# shield_v9.net
KiCad netlist of a schematic drawn in EAGLE
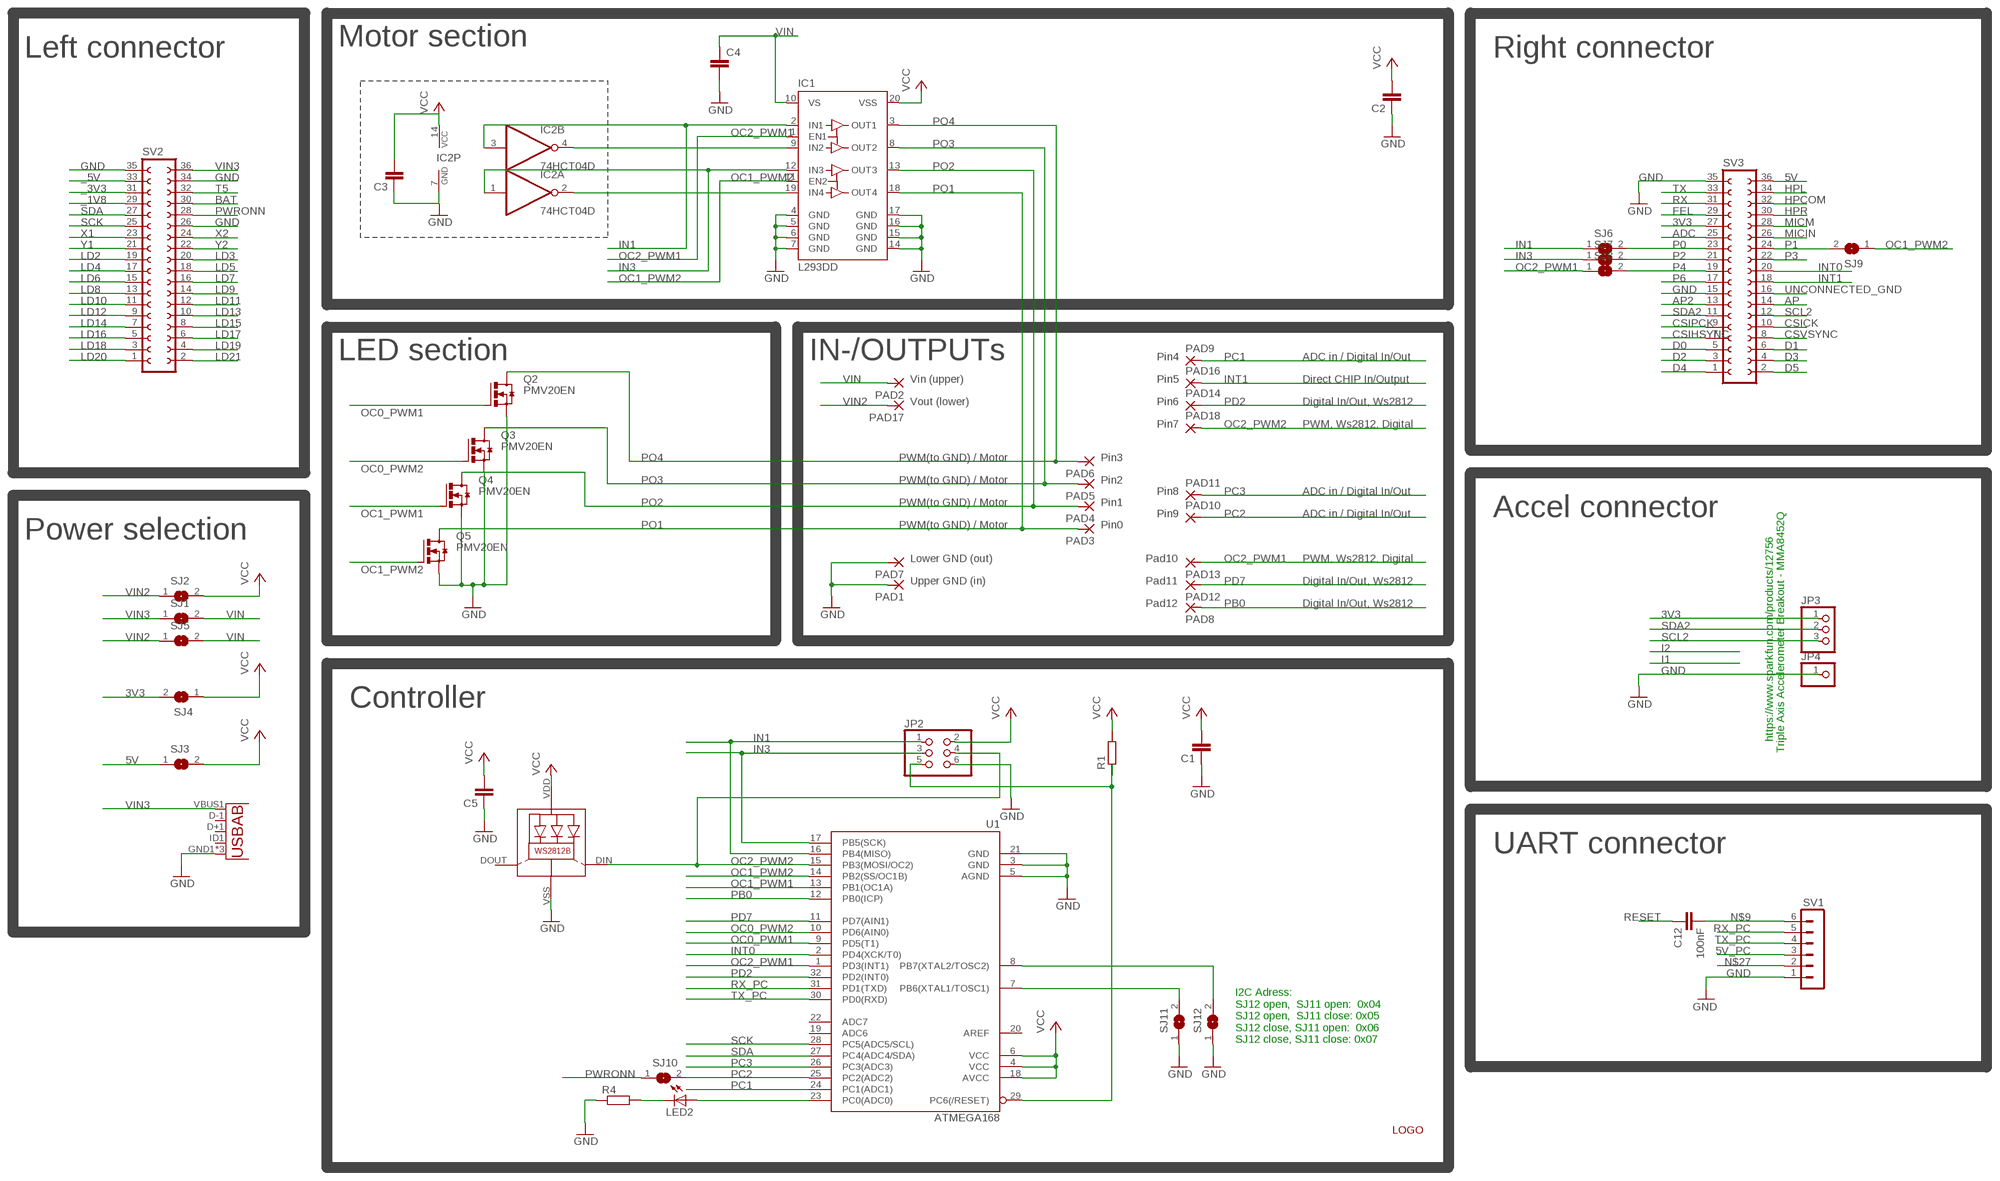
[diagram p0: schematic, sheet 1]

(export (version "E")
  (design (tool "Eeschema 10.0.6"))
  (components
    (comp (ref "C1")
      (value "C-EUC0805")
      (footprint "eagle-import:C0805")
      (libsource (lib "eagle-import") (part "C-EUC0805"))
    )
    (comp (ref "C2")
      (value "C-EUC0805")
      (footprint "eagle-import:C0805")
      (libsource (lib "eagle-import") (part "C-EUC0805"))
    )
    (comp (ref "C3")
      (value "C-EUC0805")
      (footprint "eagle-import:C0805")
      (libsource (lib "eagle-import") (part "C-EUC0805"))
    )
    (comp (ref "C4")
      (value "C-EUC1210")
      (footprint "eagle-import:C1210")
      (libsource (lib "eagle-import") (part "C-EUC1210"))
    )
    (comp (ref "C5")
      (value "C-EUC0805")
      (footprint "eagle-import:C0805")
      (libsource (lib "eagle-import") (part "C-EUC0805"))
    )
    (comp (ref "C12")
      (value "100nF")
      (footprint "eagle-import:C1206")
      (libsource (lib "eagle-import") (part "C-EUC1206"))
    )
    (comp (ref "IC1")
      (value "L293DD")
      (footprint "eagle-import:SO20")
      (libsource (lib "eagle-import") (part "L293DD"))
    )
    (comp (ref "IC2")
      (value "74HCT04D")
      (footprint "eagle-import:SO14")
      (libsource (lib "eagle-import") (part "7404DHCT"))
    )
    (comp (ref "JP2")
      (value "PINHD-2X3")
      (footprint "eagle-import:2X03")
      (libsource (lib "eagle-import") (part "PINHD-2X3"))
    )
    (comp (ref "JP3")
      (value "PINHD-1X3")
      (footprint "eagle-import:1X03")
      (libsource (lib "eagle-import") (part "PINHD-1X3"))
    )
    (comp (ref "JP4")
      (value "PINHD-1X1")
      (footprint "eagle-import:1X01")
      (libsource (lib "eagle-import") (part "PINHD-1X1"))
    )
    (comp (ref "LED1")
      (value "WS2812B")
      (footprint "eagle-import:WS2812B")
      (libsource (lib "eagle-import") (part "WS2812B"))
    )
    (comp (ref "LED2")
      (value "LEDCHIP-LED0805")
      (footprint "eagle-import:CHIP-LED0805")
      (libsource (lib "eagle-import") (part "LEDCHIP-LED0805"))
    )
    (comp (ref "PAD1")
      (value "3,17/1,3")
      (footprint "eagle-import:3,17_1,3")
      (libsource (lib "eagle-import") (part "3,17/1,3"))
    )
    (comp (ref "PAD2")
      (value "3,17/1,3")
      (footprint "eagle-import:3,17_1,3")
      (libsource (lib "eagle-import") (part "3,17/1,3"))
    )
    (comp (ref "PAD3")
      (value "3,17/1,3")
      (footprint "eagle-import:3,17_1,3")
      (libsource (lib "eagle-import") (part "3,17/1,3"))
    )
    (comp (ref "PAD4")
      (value "3,17/1,3")
      (footprint "eagle-import:3,17_1,3")
      (libsource (lib "eagle-import") (part "3,17/1,3"))
    )
    (comp (ref "PAD5")
      (value "3,17/1,3")
      (footprint "eagle-import:3,17_1,3")
      (libsource (lib "eagle-import") (part "3,17/1,3"))
    )
    (comp (ref "PAD6")
      (value "3,17/1,3")
      (footprint "eagle-import:3,17_1,3")
      (libsource (lib "eagle-import") (part "3,17/1,3"))
    )
    (comp (ref "PAD7")
      (value "3,17/1,3")
      (footprint "eagle-import:3,17_1,3")
      (libsource (lib "eagle-import") (part "3,17/1,3"))
    )
    (comp (ref "PAD8")
      (value "WIREPADSMD1,27-254")
      (footprint "eagle-import:SMD1,27-2,54")
      (libsource (lib "eagle-import") (part "WIREPADSMD1,27-254"))
    )
    (comp (ref "PAD9")
      (value "3,17/1,3")
      (footprint "eagle-import:3,17_1,3")
      (libsource (lib "eagle-import") (part "3,17/1,3"))
    )
    (comp (ref "PAD10")
      (value "3,17/1,3")
      (footprint "eagle-import:3,17_1,3")
      (libsource (lib "eagle-import") (part "3,17/1,3"))
    )
    (comp (ref "PAD11")
      (value "3,17/1,3")
      (footprint "eagle-import:3,17_1,3")
      (libsource (lib "eagle-import") (part "3,17/1,3"))
    )
    (comp (ref "PAD12")
      (value "SMD2")
      (footprint "eagle-import:SMD1,27-2,54")
      (libsource (lib "eagle-import") (part "SMD2"))
    )
    (comp (ref "PAD13")
      (value "SMD2")
      (footprint "eagle-import:SMD1,27-2,54")
      (libsource (lib "eagle-import") (part "SMD2"))
    )
    (comp (ref "PAD14")
      (value "3,17/1,3")
      (footprint "eagle-import:3,17_1,3")
      (libsource (lib "eagle-import") (part "3,17/1,3"))
    )
    (comp (ref "PAD16")
      (value "3,17/1,3")
      (footprint "eagle-import:3,17_1,3")
      (libsource (lib "eagle-import") (part "3,17/1,3"))
    )
    (comp (ref "PAD17")
      (value "3,17/1,3")
      (footprint "eagle-import:3,17_1,3")
      (libsource (lib "eagle-import") (part "3,17/1,3"))
    )
    (comp (ref "PAD18")
      (value "3,17/1,3")
      (footprint "eagle-import:3,17_1,3")
      (libsource (lib "eagle-import") (part "3,17/1,3"))
    )
    (comp (ref "Q2")
      (value "PMV20EN")
      (footprint "eagle-import:SOT223")
      (libsource (lib "eagle-import") (part "NMOSFET_SMD_223"))
    )
    (comp (ref "Q3")
      (value "PMV20EN")
      (footprint "eagle-import:SOT223")
      (libsource (lib "eagle-import") (part "NMOSFET_SMD_223"))
    )
    (comp (ref "Q4")
      (value "PMV20EN")
      (footprint "eagle-import:SOT223")
      (libsource (lib "eagle-import") (part "NMOSFET_SMD_223"))
    )
    (comp (ref "Q5")
      (value "PMV20EN")
      (footprint "eagle-import:SOT223")
      (libsource (lib "eagle-import") (part "NMOSFET_SMD_223"))
    )
    (comp (ref "R1")
      (value "R-EU_M1206")
      (footprint "eagle-import:M1206")
      (libsource (lib "eagle-import") (part "R-EU_M1206"))
    )
    (comp (ref "R4")
      (value "R-EU_M1206")
      (footprint "eagle-import:M1206")
      (libsource (lib "eagle-import") (part "R-EU_M1206"))
    )
    (comp (ref "SJ1") (value "SJ") (footprint "eagle-import:SJ") (libsource (lib "eagle-import") (part "SJ")))
    (comp (ref "SJ2") (value "SJ") (footprint "eagle-import:SJ") (libsource (lib "eagle-import") (part "SJ")))
    (comp (ref "SJ3") (value "SJ") (footprint "eagle-import:SJ") (libsource (lib "eagle-import") (part "SJ")))
    (comp (ref "SJ4") (value "SJ") (footprint "eagle-import:SJ") (libsource (lib "eagle-import") (part "SJ")))
    (comp (ref "SJ5") (value "SJ") (footprint "eagle-import:SJ") (libsource (lib "eagle-import") (part "SJ")))
    (comp (ref "SJ6") (value "SJ") (footprint "eagle-import:SJ") (libsource (lib "eagle-import") (part "SJ")))
    (comp (ref "SJ7") (value "SJ") (footprint "eagle-import:SJ") (libsource (lib "eagle-import") (part "SJ")))
    (comp (ref "SJ8") (value "SJ") (footprint "eagle-import:SJ") (libsource (lib "eagle-import") (part "SJ")))
    (comp (ref "SJ9") (value "SJ") (footprint "eagle-import:SJ") (libsource (lib "eagle-import") (part "SJ")))
    (comp (ref "SJ10")
      (value "SJ")
      (footprint "eagle-import:SJ")
      (libsource (lib "eagle-import") (part "SJ"))
    )
    (comp (ref "SJ11")
      (value "SJ")
      (footprint "eagle-import:SJ")
      (libsource (lib "eagle-import") (part "SJ"))
    )
    (comp (ref "SJ12")
      (value "SJ")
      (footprint "eagle-import:SJ")
      (libsource (lib "eagle-import") (part "SJ"))
    )
    (comp (ref "SV1")
      (value "MA06-1")
      (footprint "eagle-import:MA06-1")
      (libsource (lib "eagle-import") (part "MA06-1"))
    )
    (comp (ref "SV2")
      (value "FE18-2")
      (footprint "eagle-import:FE18-2")
      (libsource (lib "eagle-import") (part "FE18-2"))
    )
    (comp (ref "SV3")
      (value "FE18-2")
      (footprint "eagle-import:FE18-2")
      (libsource (lib "eagle-import") (part "FE18-2"))
    )
    (comp (ref "U$2")
      (value "LOGO")
      (footprint "eagle-import:LOGO")
      (libsource (lib "eagle-import") (part "LOGO"))
    )
    (comp (ref "U1")
      (value "ATMEGA168")
      (footprint "eagle-import:TQFP32-08")
      (libsource (lib "eagle-import") (part "ATMEGA168"))
    )
    (comp (ref "U2")
      (value "USB\"\"")
      (footprint "eagle-import:USB-MICRO-SMD")
      (libsource (lib "eagle-import") (part "USB{dblquote}{dblquote}"))
    )
  )
  (nets
    (net (code "1") (name "/3V3") (class "Default")
      (node (ref "JP3") (pin "1") (pinfunction "1_1") (pintype "passive"))
      (node (ref "SJ4") (pin "2") (pinfunction "2_2") (pintype "passive"))
      (node (ref "SV3") (pin "27") (pinfunction "27_27") (pintype "passive"))
    )
    (net (code "2") (name "/5V") (class "Default")
      (node (ref "SJ3") (pin "1") (pinfunction "1_1") (pintype "passive"))
      (node (ref "SV3") (pin "36") (pinfunction "36_36") (pintype "passive"))
    )
    (net (code "3") (name "/5V_PC") (class "Default")
      (node (ref "SV1") (pin "3") (pinfunction "3_3") (pintype "passive"))
    )
    (net (code "4") (name "/ADC") (class "Default")
      (node (ref "SV3") (pin "25") (pinfunction "25_25") (pintype "passive"))
    )
    (net (code "5") (name "/AP") (class "Default")
      (node (ref "SV3") (pin "14") (pinfunction "14_14") (pintype "passive"))
    )
    (net (code "6") (name "/AP2") (class "Default")
      (node (ref "SV3") (pin "13") (pinfunction "13_13") (pintype "passive"))
    )
    (net (code "7") (name "/BAT") (class "Default")
      (node (ref "SV2") (pin "30") (pinfunction "30_30") (pintype "passive"))
    )
    (net (code "8") (name "/CSICK") (class "Default")
      (node (ref "SV3") (pin "10") (pinfunction "10_10") (pintype "passive"))
    )
    (net (code "9") (name "/CSIHSYNC") (class "Default")
      (node (ref "SV3") (pin "7") (pinfunction "7_7") (pintype "passive"))
    )
    (net (code "10") (name "/CSIPCK") (class "Default")
      (node (ref "SV3") (pin "9") (pinfunction "9_9") (pintype "passive"))
    )
    (net (code "11") (name "/CSVSYNC") (class "Default")
      (node (ref "SV3") (pin "8") (pinfunction "8_8") (pintype "passive"))
    )
    (net (code "12") (name "/D0") (class "Default")
      (node (ref "SV3") (pin "5") (pinfunction "5_5") (pintype "passive"))
    )
    (net (code "13") (name "/D1") (class "Default")
      (node (ref "SV3") (pin "6") (pinfunction "6_6") (pintype "passive"))
    )
    (net (code "14") (name "/D2") (class "Default")
      (node (ref "SV3") (pin "3") (pinfunction "3_3") (pintype "passive"))
    )
    (net (code "15") (name "/D3") (class "Default")
      (node (ref "SV3") (pin "4") (pinfunction "4_4") (pintype "passive"))
    )
    (net (code "16") (name "/D4") (class "Default")
      (node (ref "SV3") (pin "1") (pinfunction "1_1") (pintype "passive"))
    )
    (net (code "17") (name "/D5") (class "Default")
      (node (ref "SV3") (pin "2") (pinfunction "2_2") (pintype "passive"))
    )
    (net (code "18") (name "/FEL") (class "Default")
      (node (ref "SV3") (pin "29") (pinfunction "29_29") (pintype "passive"))
    )
    (net (code "19") (name "/HPCOM") (class "Default")
      (node (ref "SV3") (pin "32") (pinfunction "32_32") (pintype "passive"))
    )
    (net (code "20") (name "/HPL") (class "Default")
      (node (ref "SV3") (pin "34") (pinfunction "34_34") (pintype "passive"))
    )
    (net (code "21") (name "/HPR") (class "Default")
      (node (ref "SV3") (pin "30") (pinfunction "30_30") (pintype "passive"))
    )
    (net (code "24") (name "/IN1") (class "Default")
      (node (ref "IC1") (pin "2") (pinfunction "IN1_2") (pintype "input"))
      (node (ref "IC2") (pin "3") (pinfunction "I_3") (pintype "input"))
      (node (ref "JP2") (pin "1") (pinfunction "1_1") (pintype "passive"))
      (node (ref "SJ6") (pin "1") (pinfunction "1_1") (pintype "passive"))
      (node (ref "U1") (pin "16") (pinfunction "PB4(MISO)_16") (pintype "bidirectional"))
    )
    (net (code "25") (name "/IN3") (class "Default")
      (node (ref "IC1") (pin "12") (pinfunction "IN3_12") (pintype "input"))
      (node (ref "IC2") (pin "1") (pinfunction "I_1") (pintype "input"))
      (node (ref "JP2") (pin "3") (pinfunction "3_3") (pintype "passive"))
      (node (ref "SJ7") (pin "1") (pinfunction "1_1") (pintype "passive"))
      (node (ref "U1") (pin "17") (pinfunction "PB5(SCK)_17") (pintype "bidirectional"))
    )
    (net (code "26") (name "/INT0") (class "Default")
      (node (ref "SV3") (pin "20") (pinfunction "20_20") (pintype "passive"))
      (node (ref "U1") (pin "2") (pinfunction "PD4(XCK/T0)_2") (pintype "bidirectional"))
    )
    (net (code "27") (name "/INT1") (class "Default")
      (node (ref "PAD16") (pin "1") (pinfunction "P_1") (pintype "passive"))
      (node (ref "SV3") (pin "18") (pinfunction "18_18") (pintype "passive"))
    )
    (net (code "28") (name "/LD2") (class "Default")
      (node (ref "SV2") (pin "19") (pinfunction "19_19") (pintype "passive"))
    )
    (net (code "29") (name "/LD3") (class "Default")
      (node (ref "SV2") (pin "20") (pinfunction "20_20") (pintype "passive"))
    )
    (net (code "30") (name "/LD4") (class "Default")
      (node (ref "SV2") (pin "17") (pinfunction "17_17") (pintype "passive"))
    )
    (net (code "31") (name "/LD5") (class "Default")
      (node (ref "SV2") (pin "18") (pinfunction "18_18") (pintype "passive"))
    )
    (net (code "32") (name "/LD6") (class "Default")
      (node (ref "SV2") (pin "15") (pinfunction "15_15") (pintype "passive"))
    )
    (net (code "33") (name "/LD7") (class "Default")
      (node (ref "SV2") (pin "16") (pinfunction "16_16") (pintype "passive"))
    )
    (net (code "34") (name "/LD8") (class "Default")
      (node (ref "SV2") (pin "13") (pinfunction "13_13") (pintype "passive"))
    )
    (net (code "35") (name "/LD9") (class "Default")
      (node (ref "SV2") (pin "14") (pinfunction "14_14") (pintype "passive"))
    )
    (net (code "36") (name "/LD10") (class "Default")
      (node (ref "SV2") (pin "11") (pinfunction "11_11") (pintype "passive"))
    )
    (net (code "37") (name "/LD11") (class "Default")
      (node (ref "SV2") (pin "12") (pinfunction "12_12") (pintype "passive"))
    )
    (net (code "38") (name "/LD12") (class "Default")
      (node (ref "SV2") (pin "9") (pinfunction "9_9") (pintype "passive"))
    )
    (net (code "39") (name "/LD13") (class "Default")
      (node (ref "SV2") (pin "10") (pinfunction "10_10") (pintype "passive"))
    )
    (net (code "40") (name "/LD14") (class "Default")
      (node (ref "SV2") (pin "7") (pinfunction "7_7") (pintype "passive"))
    )
    (net (code "41") (name "/LD15") (class "Default")
      (node (ref "SV2") (pin "8") (pinfunction "8_8") (pintype "passive"))
    )
    (net (code "42") (name "/LD16") (class "Default")
      (node (ref "SV2") (pin "5") (pinfunction "5_5") (pintype "passive"))
    )
    (net (code "43") (name "/LD17") (class "Default")
      (node (ref "SV2") (pin "6") (pinfunction "6_6") (pintype "passive"))
    )
    (net (code "44") (name "/LD18") (class "Default")
      (node (ref "SV2") (pin "3") (pinfunction "3_3") (pintype "passive"))
    )
    (net (code "45") (name "/LD19") (class "Default")
      (node (ref "SV2") (pin "4") (pinfunction "4_4") (pintype "passive"))
    )
    (net (code "46") (name "/LD20") (class "Default")
      (node (ref "SV2") (pin "1") (pinfunction "1_1") (pintype "passive"))
    )
    (net (code "47") (name "/LD21") (class "Default")
      (node (ref "SV2") (pin "2") (pinfunction "2_2") (pintype "passive"))
    )
    (net (code "48") (name "/MICIN") (class "Default")
      (node (ref "SV3") (pin "26") (pinfunction "26_26") (pintype "passive"))
    )
    (net (code "49") (name "/MICM") (class "Default")
      (node (ref "SV3") (pin "28") (pinfunction "28_28") (pintype "passive"))
    )
    (net (code "50") (name "/N$9") (class "Default")
      (node (ref "C12") (pin "2") (pinfunction "2_2") (pintype "passive"))
      (node (ref "SV1") (pin "6") (pinfunction "6_6") (pintype "passive"))
    )
    (net (code "51") (name "/N$27") (class "Default")
      (node (ref "SV1") (pin "2") (pinfunction "2_2") (pintype "passive"))
    )
    (net (code "52") (name "/OC0_PWM1") (class "Default")
      (node (ref "Q2") (pin "1") (pinfunction "G_1") (pintype "passive"))
      (node (ref "U1") (pin "9") (pinfunction "PD5(T1)_9") (pintype "bidirectional"))
    )
    (net (code "53") (name "/OC0_PWM2") (class "Default")
      (node (ref "Q3") (pin "1") (pinfunction "G_1") (pintype "passive"))
      (node (ref "U1") (pin "10") (pinfunction "PD6(AIN0)_10") (pintype "bidirectional"))
    )
    (net (code "54") (name "/OC1_PWM1") (class "Default")
      (node (ref "Q4") (pin "1") (pinfunction "G_1") (pintype "passive"))
      (node (ref "U1") (pin "13") (pinfunction "PB1(OC1A)_13") (pintype "bidirectional"))
    )
    (net (code "55") (name "/OC1_PWM2") (class "Default")
      (node (ref "IC1") (pin "11") (pinfunction "EN2_11") (pintype "input"))
      (node (ref "Q5") (pin "1") (pinfunction "G_1") (pintype "passive"))
      (node (ref "SJ9") (pin "1") (pinfunction "1_1") (pintype "passive"))
      (node (ref "U1") (pin "14") (pinfunction "PB2(SS/OC1B)_14") (pintype "bidirectional"))
    )
    (net (code "56") (name "/OC2_PWM1") (class "Default")
      (node (ref "IC1") (pin "1") (pinfunction "EN1_1") (pintype "input"))
      (node (ref "PAD13") (pin "1") (pinfunction "P_1") (pintype "passive"))
      (node (ref "SJ8") (pin "1") (pinfunction "1_1") (pintype "passive"))
      (node (ref "U1") (pin "1") (pinfunction "PD3(INT1)_1") (pintype "bidirectional"))
    )
    (net (code "57") (name "/OC2_PWM2") (class "Default")
      (node (ref "JP2") (pin "4") (pinfunction "4_4") (pintype "passive"))
      (node (ref "LED1") (pin "DIN") (pinfunction "DI_DIN") (pintype "input"))
      (node (ref "PAD18") (pin "1") (pinfunction "P_1") (pintype "passive"))
      (node (ref "U1") (pin "15") (pinfunction "PB3(MOSI/OC2)_15") (pintype "bidirectional"))
    )
    (net (code "58") (name "/P0") (class "Default")
      (node (ref "SJ6") (pin "2") (pinfunction "2_2") (pintype "passive"))
      (node (ref "SV3") (pin "23") (pinfunction "23_23") (pintype "passive"))
    )
    (net (code "59") (name "/P1") (class "Default")
      (node (ref "SJ9") (pin "2") (pinfunction "2_2") (pintype "passive"))
      (node (ref "SV3") (pin "24") (pinfunction "24_24") (pintype "passive"))
    )
    (net (code "60") (name "/P2") (class "Default")
      (node (ref "SJ7") (pin "2") (pinfunction "2_2") (pintype "passive"))
      (node (ref "SV3") (pin "21") (pinfunction "21_21") (pintype "passive"))
    )
    (net (code "61") (name "/P3") (class "Default")
      (node (ref "SV3") (pin "22") (pinfunction "22_22") (pintype "passive"))
    )
    (net (code "62") (name "/P4") (class "Default")
      (node (ref "SJ8") (pin "2") (pinfunction "2_2") (pintype "passive"))
      (node (ref "SV3") (pin "19") (pinfunction "19_19") (pintype "passive"))
    )
    (net (code "63") (name "/P6") (class "Default")
      (node (ref "SV3") (pin "17") (pinfunction "17_17") (pintype "passive"))
    )
    (net (code "64") (name "/PB0") (class "Default")
      (node (ref "PAD8") (pin "1") (pinfunction "P_1") (pintype "passive"))
      (node (ref "U1") (pin "12") (pinfunction "PB0(ICP)_12") (pintype "bidirectional"))
    )
    (net (code "65") (name "/PC1") (class "Default")
      (node (ref "PAD9") (pin "1") (pinfunction "P_1") (pintype "passive"))
      (node (ref "U1") (pin "24") (pinfunction "PC1(ADC1)_24") (pintype "bidirectional"))
    )
    (net (code "66") (name "/PC2") (class "Default")
      (node (ref "PAD10") (pin "1") (pinfunction "P_1") (pintype "passive"))
      (node (ref "SJ10") (pin "2") (pinfunction "2_2") (pintype "passive"))
      (node (ref "U1") (pin "25") (pinfunction "PC2(ADC2)_25") (pintype "bidirectional"))
    )
    (net (code "67") (name "/PC3") (class "Default")
      (node (ref "PAD11") (pin "1") (pinfunction "P_1") (pintype "passive"))
      (node (ref "U1") (pin "26") (pinfunction "PC3(ADC3)_26") (pintype "bidirectional"))
    )
    (net (code "68") (name "/PD2") (class "Default")
      (node (ref "PAD14") (pin "1") (pinfunction "P_1") (pintype "passive"))
      (node (ref "U1") (pin "32") (pinfunction "PD2(INT0)_32") (pintype "bidirectional"))
    )
    (net (code "69") (name "/PD7") (class "Default")
      (node (ref "PAD12") (pin "1") (pinfunction "P_1") (pintype "passive"))
      (node (ref "U1") (pin "11") (pinfunction "PD7(AIN1)_11") (pintype "bidirectional"))
    )
    (net (code "70") (name "/PO1") (class "Default")
      (node (ref "IC1") (pin "18") (pinfunction "OUT4_18") (pintype "output"))
      (node (ref "PAD3") (pin "1") (pinfunction "P_1") (pintype "passive"))
      (node (ref "Q5") (pin "2") (pinfunction "D_2") (pintype "passive"))
      (node (ref "Q5") (pin "4") (pinfunction "D_4") (pintype "passive"))
    )
    (net (code "71") (name "/PO2") (class "Default")
      (node (ref "IC1") (pin "13") (pinfunction "OUT3_13") (pintype "output"))
      (node (ref "PAD4") (pin "1") (pinfunction "P_1") (pintype "passive"))
      (node (ref "Q4") (pin "2") (pinfunction "D_2") (pintype "passive"))
      (node (ref "Q4") (pin "4") (pinfunction "D_4") (pintype "passive"))
    )
    (net (code "72") (name "/PO3") (class "Default")
      (node (ref "IC1") (pin "8") (pinfunction "OUT2_8") (pintype "output"))
      (node (ref "PAD5") (pin "1") (pinfunction "P_1") (pintype "passive"))
      (node (ref "Q3") (pin "2") (pinfunction "D_2") (pintype "passive"))
      (node (ref "Q3") (pin "4") (pinfunction "D_4") (pintype "passive"))
    )
    (net (code "73") (name "/PO4") (class "Default")
      (node (ref "IC1") (pin "3") (pinfunction "OUT1_3") (pintype "output"))
      (node (ref "PAD6") (pin "1") (pinfunction "P_1") (pintype "passive"))
      (node (ref "Q2") (pin "2") (pinfunction "D_2") (pintype "passive"))
      (node (ref "Q2") (pin "4") (pinfunction "D_4") (pintype "passive"))
    )
    (net (code "74") (name "/PWRONN") (class "Default")
      (node (ref "SJ10") (pin "1") (pinfunction "1_1") (pintype "passive"))
      (node (ref "SV2") (pin "28") (pinfunction "28_28") (pintype "passive"))
    )
    (net (code "75") (name "/RESET") (class "Default")
      (node (ref "C12") (pin "1") (pinfunction "1_1") (pintype "passive"))
      (node (ref "JP2") (pin "5") (pinfunction "5_5") (pintype "passive"))
      (node (ref "R1") (pin "1") (pinfunction "1_1") (pintype "passive"))
      (node (ref "U1") (pin "29") (pinfunction "PC6(/RESET)_29") (pintype "bidirectional"))
    )
    (net (code "76") (name "/RX") (class "Default")
      (node (ref "SV3") (pin "31") (pinfunction "31_31") (pintype "passive"))
    )
    (net (code "77") (name "/RX_PC") (class "Default")
      (node (ref "SV1") (pin "5") (pinfunction "5_5") (pintype "passive"))
      (node (ref "U1") (pin "31") (pinfunction "PD1(TXD)_31") (pintype "bidirectional"))
    )
    (net (code "78") (name "/SCK") (class "Default")
      (node (ref "SV2") (pin "25") (pinfunction "25_25") (pintype "passive"))
      (node (ref "U1") (pin "28") (pinfunction "PC5(ADC5/SCL)_28") (pintype "bidirectional"))
    )
    (net (code "79") (name "/SCL2") (class "Default")
      (node (ref "JP3") (pin "3") (pinfunction "3_3") (pintype "passive"))
      (node (ref "SV3") (pin "12") (pinfunction "12_12") (pintype "passive"))
    )
    (net (code "80") (name "/SDA") (class "Default")
      (node (ref "SV2") (pin "27") (pinfunction "27_27") (pintype "passive"))
      (node (ref "U1") (pin "27") (pinfunction "PC4(ADC4/SDA)_27") (pintype "bidirectional"))
    )
    (net (code "81") (name "/SDA2") (class "Default")
      (node (ref "JP3") (pin "2") (pinfunction "2_2") (pintype "passive"))
      (node (ref "SV3") (pin "11") (pinfunction "11_11") (pintype "passive"))
    )
    (net (code "82") (name "/T5") (class "Default")
      (node (ref "SV2") (pin "32") (pinfunction "32_32") (pintype "passive"))
    )
    (net (code "83") (name "/TX") (class "Default")
      (node (ref "SV3") (pin "33") (pinfunction "33_33") (pintype "passive"))
    )
    (net (code "84") (name "/TX_PC") (class "Default")
      (node (ref "SV1") (pin "4") (pinfunction "4_4") (pintype "passive"))
      (node (ref "U1") (pin "30") (pinfunction "PD0(RXD)_30") (pintype "bidirectional"))
    )
    (net (code "85") (name "/UNCONNECTED_GND") (class "Default")
      (node (ref "SV3") (pin "16") (pinfunction "16_16") (pintype "passive"))
    )
    (net (code "86") (name "/VIN") (class "Default")
      (node (ref "C4") (pin "1") (pinfunction "1_1") (pintype "passive"))
      (node (ref "IC1") (pin "10") (pinfunction "VS_10") (pintype "power_in"))
      (node (ref "PAD2") (pin "1") (pinfunction "P_1") (pintype "passive"))
      (node (ref "SJ1") (pin "2") (pinfunction "2_2") (pintype "passive"))
      (node (ref "SJ5") (pin "2") (pinfunction "2_2") (pintype "passive"))
    )
    (net (code "87") (name "/VIN2") (class "Default")
      (node (ref "PAD17") (pin "1") (pinfunction "P_1") (pintype "passive"))
      (node (ref "SJ2") (pin "1") (pinfunction "1_1") (pintype "passive"))
      (node (ref "SJ5") (pin "1") (pinfunction "1_1") (pintype "passive"))
    )
    (net (code "88") (name "/VIN3") (class "Default")
      (node (ref "SJ1") (pin "1") (pinfunction "1_1") (pintype "passive"))
      (node (ref "SV2") (pin "36") (pinfunction "36_36") (pintype "passive"))
      (node (ref "U2") (pin "VBUS1") (pinfunction "VBUS_VBUS1") (pintype "bidirectional"))
    )
    (net (code "89") (name "/X1") (class "Default")
      (node (ref "SV2") (pin "23") (pinfunction "23_23") (pintype "passive"))
    )
    (net (code "90") (name "/X2") (class "Default")
      (node (ref "SV2") (pin "24") (pinfunction "24_24") (pintype "passive"))
    )
    (net (code "91") (name "/Y1") (class "Default")
      (node (ref "SV2") (pin "21") (pinfunction "21_21") (pintype "passive"))
    )
    (net (code "92") (name "/Y2") (class "Default")
      (node (ref "SV2") (pin "22") (pinfunction "22_22") (pintype "passive"))
    )
    (net (code "93") (name "/_1V8") (class "Default")
      (node (ref "SV2") (pin "29") (pinfunction "29_29") (pintype "passive"))
    )
    (net (code "94") (name "/_3V3") (class "Default")
      (node (ref "SV2") (pin "31") (pinfunction "31_31") (pintype "passive"))
    )
    (net (code "95") (name "/_5V") (class "Default")
      (node (ref "SV2") (pin "33") (pinfunction "33_33") (pintype "passive"))
    )
    (net (code "96") (name "GND") (class "Default")
      (node (ref "C1") (pin "1") (pinfunction "1_1") (pintype "passive"))
      (node (ref "C2") (pin "1") (pinfunction "1_1") (pintype "passive"))
      (node (ref "C3") (pin "1") (pinfunction "1_1") (pintype "passive"))
      (node (ref "C4") (pin "2") (pinfunction "2_2") (pintype "passive"))
      (node (ref "C5") (pin "1") (pinfunction "1_1") (pintype "passive"))
      (node (ref "IC1") (pin "14") (pinfunction "GND_14") (pintype "power_in"))
      (node (ref "IC1") (pin "15") (pinfunction "GND_15") (pintype "power_in"))
      (node (ref "IC1") (pin "16") (pinfunction "GND_16") (pintype "power_in"))
      (node (ref "IC1") (pin "17") (pinfunction "GND_17") (pintype "power_in"))
      (node (ref "IC1") (pin "4") (pinfunction "GND_4") (pintype "power_in"))
      (node (ref "IC1") (pin "5") (pinfunction "GND_5") (pintype "power_in"))
      (node (ref "IC1") (pin "6") (pinfunction "GND_6") (pintype "power_in"))
      (node (ref "IC1") (pin "7") (pinfunction "GND_7") (pintype "power_in"))
      (node (ref "IC2") (pin "7") (pinfunction "GND_7") (pintype "power_in"))
      (node (ref "JP2") (pin "6") (pinfunction "6_6") (pintype "passive"))
      (node (ref "JP4") (pin "1") (pinfunction "1_1") (pintype "passive"))
      (node (ref "LED1") (pin "VSS") (pinfunction "GND_VSS") (pintype "power_in"))
      (node (ref "PAD1") (pin "1") (pinfunction "P_1") (pintype "passive"))
      (node (ref "PAD7") (pin "1") (pinfunction "P_1") (pintype "passive"))
      (node (ref "Q2") (pin "3") (pinfunction "S_3") (pintype "passive"))
      (node (ref "Q3") (pin "3") (pinfunction "S_3") (pintype "passive"))
      (node (ref "Q4") (pin "3") (pinfunction "S_3") (pintype "passive"))
      (node (ref "Q5") (pin "3") (pinfunction "S_3") (pintype "passive"))
      (node (ref "R4") (pin "1") (pinfunction "1_1") (pintype "passive"))
      (node (ref "SJ11") (pin "1") (pinfunction "1_1") (pintype "passive"))
      (node (ref "SJ12") (pin "1") (pinfunction "1_1") (pintype "passive"))
      (node (ref "SV1") (pin "1") (pinfunction "1_1") (pintype "passive"))
      (node (ref "SV2") (pin "26") (pinfunction "26_26") (pintype "passive"))
      (node (ref "SV2") (pin "34") (pinfunction "34_34") (pintype "passive"))
      (node (ref "SV2") (pin "35") (pinfunction "35_35") (pintype "passive"))
      (node (ref "SV3") (pin "15") (pinfunction "15_15") (pintype "passive"))
      (node (ref "SV3") (pin "35") (pinfunction "35_35") (pintype "passive"))
      (node (ref "U1") (pin "21") (pinfunction "GND_21") (pintype "bidirectional"))
      (node (ref "U1") (pin "3") (pinfunction "GND_3") (pintype "bidirectional"))
      (node (ref "U1") (pin "5") (pinfunction "AGND_5") (pintype "bidirectional"))
      (node (ref "U2") (pin "GND1") (pinfunction "GND_GND1") (pintype "bidirectional"))
      (node (ref "U2") (pin "GND2") (pinfunction "GND_GND2") (pintype "bidirectional"))
      (node (ref "U2") (pin "GND3") (pinfunction "GND_GND3") (pintype "bidirectional"))
    )
    (net (code "97") (name "Net-(IC1-IN2)") (class "Default")
      (node (ref "IC1") (pin "9") (pinfunction "IN2_9") (pintype "input"))
      (node (ref "IC2") (pin "4") (pinfunction "O_4") (pintype "output"))
    )
    (net (code "98") (name "Net-(IC1-IN4)") (class "Default")
      (node (ref "IC1") (pin "19") (pinfunction "IN4_19") (pintype "input"))
      (node (ref "IC2") (pin "2") (pinfunction "O_2") (pintype "output"))
    )
    (net (code "99") (name "Net-(LED2-PadC)") (class "Default")
      (node (ref "LED2") (pin "C") (pinfunction "C_C") (pintype "passive"))
      (node (ref "R4") (pin "2") (pinfunction "2_2") (pintype "passive"))
    )
    (net (code "100") (name "Net-(U1-PB6(XTAL1{slash}TOSC1))") (class "Default")
      (node (ref "SJ11") (pin "2") (pinfunction "2_2") (pintype "passive"))
      (node (ref "U1") (pin "7") (pinfunction "PB6(XTAL1/TOSC1)_7") (pintype "bidirectional"))
    )
    (net (code "101") (name "Net-(U1-PB7(XTAL2{slash}TOSC2))") (class "Default")
      (node (ref "SJ12") (pin "2") (pinfunction "2_2") (pintype "passive"))
      (node (ref "U1") (pin "8") (pinfunction "PB7(XTAL2/TOSC2)_8") (pintype "bidirectional"))
    )
    (net (code "102") (name "Net-(U1-PC0(ADC0))") (class "Default")
      (node (ref "LED2") (pin "A") (pinfunction "A_A") (pintype "passive"))
      (node (ref "U1") (pin "23") (pinfunction "PC0(ADC0)_23") (pintype "bidirectional"))
    )
    (net (code "103") (name "VCC") (class "Default")
      (node (ref "C1") (pin "2") (pinfunction "2_2") (pintype "passive"))
      (node (ref "C2") (pin "2") (pinfunction "2_2") (pintype "passive"))
      (node (ref "C3") (pin "2") (pinfunction "2_2") (pintype "passive"))
      (node (ref "C5") (pin "2") (pinfunction "2_2") (pintype "passive"))
      (node (ref "IC1") (pin "20") (pinfunction "VSS_20") (pintype "power_in"))
      (node (ref "IC2") (pin "14") (pinfunction "VCC_14") (pintype "power_in"))
      (node (ref "JP2") (pin "2") (pinfunction "2_2") (pintype "passive"))
      (node (ref "LED1") (pin "VDD") (pinfunction "VDD_VDD") (pintype "power_in"))
      (node (ref "R1") (pin "2") (pinfunction "2_2") (pintype "passive"))
      (node (ref "SJ2") (pin "2") (pinfunction "2_2") (pintype "passive"))
      (node (ref "SJ3") (pin "2") (pinfunction "2_2") (pintype "passive"))
      (node (ref "SJ4") (pin "1") (pinfunction "1_1") (pintype "passive"))
      (node (ref "U1") (pin "18") (pinfunction "AVCC_18") (pintype "bidirectional"))
      (node (ref "U1") (pin "4") (pinfunction "VCC_4") (pintype "bidirectional"))
      (node (ref "U1") (pin "6") (pinfunction "VCC_6") (pintype "bidirectional"))
    )
    (net (code "104") (name "unconnected-(LED1-DO-PadDOUT)") (class "Default")
      (node (ref "LED1") (pin "DOUT") (pinfunction "DO_DOUT") (pintype "output"))
    )
    (net (code "105") (name "unconnected-(U1-ADC6-Pad19)") (class "Default")
      (node (ref "U1") (pin "19") (pinfunction "ADC6_19") (pintype "bidirectional"))
    )
    (net (code "106") (name "unconnected-(U1-ADC7-Pad22)") (class "Default")
      (node (ref "U1") (pin "22") (pinfunction "ADC7_22") (pintype "bidirectional"))
    )
    (net (code "107") (name "unconnected-(U1-AREF-Pad20)") (class "Default")
      (node (ref "U1") (pin "20") (pinfunction "AREF_20") (pintype "bidirectional"))
    )
    (net (code "108") (name "unconnected-(U2-D+-PadD+1)") (class "Default")
      (node (ref "U2") (pin "D+1") (pinfunction "D+_D+1") (pintype "bidirectional"))
    )
    (net (code "109") (name "unconnected-(U2-D--PadD-1)") (class "Default")
      (node (ref "U2") (pin "D-1") (pinfunction "D-_D-1") (pintype "bidirectional"))
    )
    (net (code "110") (name "unconnected-(U2-USBID-PadID1)") (class "Default")
      (node (ref "U2") (pin "ID1") (pinfunction "USBID_ID1") (pintype "bidirectional"))
    )
  )
)
